# Lipo_Solar_Charger.net
KiCad netlist of a schematic drawn in Altium Designer
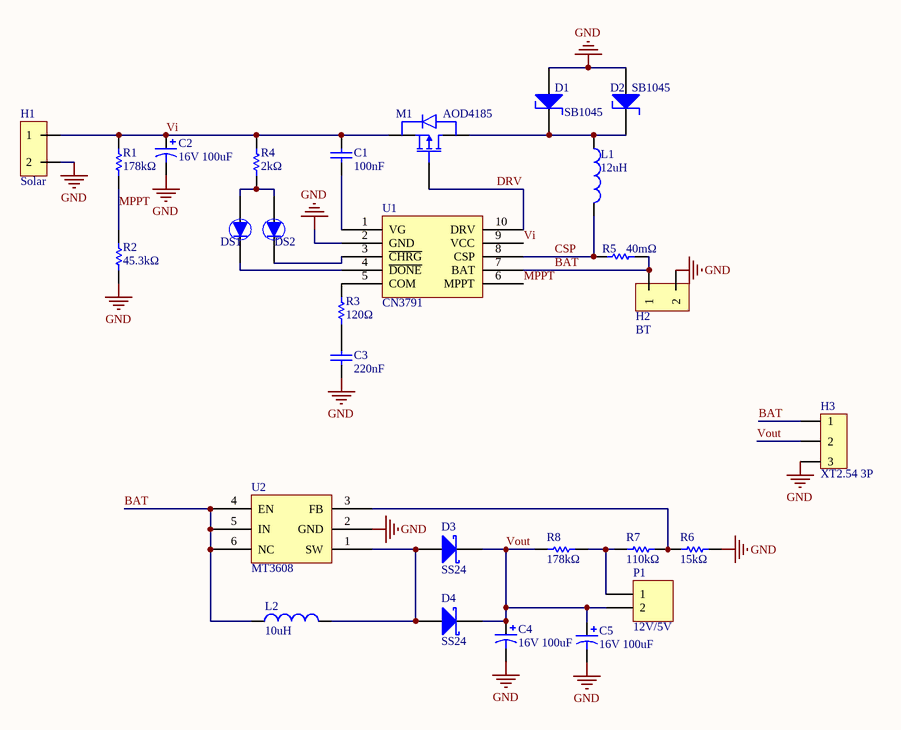
[diagram p0: Lipo_Solar_Charger.SchDoc]

(export (version "E")
  (design (tool "Eeschema 10.0.6"))
  (components
    (comp (ref "C1") (value "100nF") (footprint "0603") (libsource (lib "澄 library") (part "cap2")))
    (comp (ref "C2")
      (value "16V 100uF")
      (footprint "7343 Tantalum Capacitor")
      (description "有極性電容")
      (libsource (lib "澄 library") (part "cap"))
    )
    (comp (ref "C3") (value "220nF") (footprint "0603") (libsource (lib "澄 library") (part "cap2")))
    (comp (ref "C4")
      (value "16V 100uF")
      (footprint "7343 Tantalum Capacitor")
      (description "有極性電容")
      (libsource (lib "澄 library") (part "cap"))
    )
    (comp (ref "C5")
      (value "16V 100uF")
      (footprint "7343 Tantalum Capacitor")
      (description "有極性電容")
      (libsource (lib "澄 library") (part "cap"))
    )
    (comp (ref "D1")
      (value "SB1045")
      (footprint "TO-277")
      (description "10.0A SCHOTTKY BARRIER RECTIFIER")
      (libsource (lib "澄 library") (part "SB1045"))
    )
    (comp (ref "D2")
      (value "SB1045")
      (footprint "TO-277")
      (description "10.0A SCHOTTKY BARRIER RECTIFIER")
      (libsource (lib "澄 library") (part "SB1045"))
    )
    (comp (ref "D3")
      (value "SS24")
      (footprint "SMD Diode SMB")
      (description "Schottky Rectifier")
      (libsource (lib "澄 library") (part "DIODE"))
    )
    (comp (ref "D4")
      (value "SS24")
      (footprint "SMD Diode SMB")
      (description "Schottky Rectifier")
      (libsource (lib "澄 library") (part "DIODE"))
    )
    (comp (ref "DS1") (value "LED") (footprint "0603_LED") (libsource (lib "澄 library") (part "LED")))
    (comp (ref "DS2") (value "LED") (footprint "0603_LED") (libsource (lib "澄 library") (part "LED")))
    (comp (ref "H1") (value "Solar") (footprint "XH2.54 2P") (libsource (lib "") (part "XH2.54 2P_1")))
    (comp (ref "H2") (value "BT") (footprint "XH2.54 2P") (libsource (lib "澄 library") (part "XH2.54 2P")))
    (comp (ref "H3")
      (value "XT2.54 3P")
      (footprint "XH2.54 3P")
      (libsource (lib "澄 library") (part "XH2.54 3P"))
    )
    (comp (ref "L1") (value "12uH") (footprint "CDEP147") (libsource (lib "澄 library") (part "inductor_1")))
    (comp (ref "L2") (value "10uH") (footprint "CD75") (libsource (lib "澄 library") (part "inductor_1")))
    (comp (ref "M1")
      (value "AOD4185")
      (footprint "TO-252AA")
      (description "P-Channel Enhancement Mode Field Effect Transistor")
      (libsource (lib "澄 library") (part "AOD4185"))
    )
    (comp (ref "P1")
      (value "12V/5V")
      (footprint "HDR1X2")
      (description "Header, 2-Pin")
      (fields (field (name "PUBLISHER") "Altium Limited"))
      (libsource (lib "Miscellaneous Connectors") (part "Header 2"))
    )
    (comp (ref "R1")
      (value "178kΩ")
      (footprint "1608[0603]")
      (description "Resistor")
      (fields (field (name "PUBLISHER") "Altium Limited"))
      (libsource (lib "myLib2009") (part "Res"))
    )
    (comp (ref "R2")
      (value "45.3kΩ")
      (footprint "1608[0603]")
      (description "Resistor")
      (fields (field (name "PUBLISHER") "Altium Limited"))
      (libsource (lib "myLib2009") (part "Res"))
    )
    (comp (ref "R3")
      (value "120Ω")
      (footprint "1608[0603]")
      (description "Resistor")
      (fields (field (name "PUBLISHER") "Altium Limited"))
      (libsource (lib "myLib2009") (part "Res"))
    )
    (comp (ref "R4")
      (value "2kΩ")
      (footprint "1608[0603]")
      (description "Resistor")
      (fields (field (name "PUBLISHER") "Altium Limited"))
      (libsource (lib "myLib2009") (part "Res"))
    )
    (comp (ref "R5")
      (value "40mΩ")
      (footprint "2512[6432]")
      (description "R sense")
      (libsource (lib "澄 library") (part "Res"))
    )
    (comp (ref "R6")
      (value "15kΩ")
      (footprint "1608[0603]")
      (description "Resistor")
      (fields (field (name "PUBLISHER") "Altium Limited"))
      (libsource (lib "myLib2009") (part "Res"))
    )
    (comp (ref "R7")
      (value "110kΩ")
      (footprint "1608[0603]")
      (description "Resistor")
      (fields (field (name "PUBLISHER") "Altium Limited"))
      (libsource (lib "myLib2009") (part "Res"))
    )
    (comp (ref "R8")
      (value "178kΩ")
      (footprint "1608[0603]")
      (description "Resistor")
      (fields (field (name "PUBLISHER") "Altium Limited"))
      (libsource (lib "myLib2009") (part "Res"))
    )
    (comp (ref "U1")
      (value "CN3791")
      (footprint "SOIC100P600X175-10N")
      (description "4A, Standalone Li-ion Battery Charger IC  With Photovoltaic Cell MPPT Function")
      (libsource (lib "澄 library") (part "CN3791"))
    )
    (comp (ref "U2")
      (value "MT3608")
      (footprint "SOT23-6_L")
      (description "High Efficiency 1.2MHz  2A Step Up Converter")
      (libsource (lib "澄 library") (part "MT3608"))
    )
  )
  (nets
    (net (code "1") (name "/BAT") (class "Default")
      (node (ref "H2") (pin "1") (pinfunction "1_1") (pintype "power_in"))
      (node (ref "H3") (pin "1") (pinfunction "1_1") (pintype "passive"))
      (node (ref "L2") (pin "1") (pinfunction "1_1") (pintype "passive"))
      (node (ref "R5") (pin "1") (pinfunction "1_1") (pintype "passive"))
      (node (ref "U1") (pin "7") (pinfunction "BAT_7") (pintype "passive"))
      (node (ref "U2") (pin "4") (pinfunction "EN_4") (pintype "passive"))
      (node (ref "U2") (pin "5") (pinfunction "IN_5") (pintype "passive"))
      (node (ref "U2") (pin "6") (pinfunction "NC_6") (pintype "passive"))
    )
    (net (code "2") (name "/CSP") (class "Default")
      (node (ref "L1") (pin "2") (pinfunction "2_2") (pintype "passive"))
      (node (ref "R5") (pin "2") (pinfunction "2_2") (pintype "passive"))
      (node (ref "U1") (pin "8") (pinfunction "CSP_8") (pintype "passive"))
    )
    (net (code "3") (name "/DRV") (class "Default")
      (node (ref "M1") (pin "1") (pinfunction "G_1") (pintype "passive"))
      (node (ref "U1") (pin "10") (pinfunction "DRV_10") (pintype "passive"))
    )
    (net (code "4") (name "/MPPT") (class "Default")
      (node (ref "R1") (pin "1") (pinfunction "1_1") (pintype "passive"))
      (node (ref "R2") (pin "2") (pinfunction "2_2") (pintype "passive"))
      (node (ref "U1") (pin "6") (pinfunction "MPPT_6") (pintype "passive"))
    )
    (net (code "5") (name "/Vi") (class "Default")
      (node (ref "C1") (pin "2") (pinfunction "2_2") (pintype "passive"))
      (node (ref "C2") (pin "1") (pinfunction "1_1") (pintype "passive"))
      (node (ref "H1") (pin "1") (pinfunction "1_1") (pintype "power_in"))
      (node (ref "M1") (pin "3") (pinfunction "S_3") (pintype "passive"))
      (node (ref "R1") (pin "2") (pinfunction "2_2") (pintype "passive"))
      (node (ref "R4") (pin "2") (pinfunction "2_2") (pintype "passive"))
      (node (ref "U1") (pin "9") (pinfunction "VCC_9") (pintype "passive"))
    )
    (net (code "6") (name "/Vout") (class "Default")
      (node (ref "C4") (pin "1") (pinfunction "1_1") (pintype "passive"))
      (node (ref "C5") (pin "1") (pinfunction "1_1") (pintype "passive"))
      (node (ref "D3") (pin "2") (pinfunction "K_2") (pintype "passive"))
      (node (ref "D4") (pin "2") (pinfunction "K_2") (pintype "passive"))
      (node (ref "H3") (pin "2") (pinfunction "2_2") (pintype "passive"))
      (node (ref "P1") (pin "2") (pinfunction "2_2") (pintype "passive"))
      (node (ref "R8") (pin "2") (pinfunction "2_2") (pintype "passive"))
    )
    (net (code "7") (name "GND") (class "Default")
      (node (ref "C2") (pin "2") (pinfunction "2_2") (pintype "passive"))
      (node (ref "C3") (pin "1") (pinfunction "1_1") (pintype "passive"))
      (node (ref "C4") (pin "2") (pinfunction "2_2") (pintype "passive"))
      (node (ref "C5") (pin "2") (pinfunction "2_2") (pintype "passive"))
      (node (ref "D1") (pin "1") (pinfunction "A_1") (pintype "passive"))
      (node (ref "D2") (pin "1") (pinfunction "A_1") (pintype "passive"))
      (node (ref "H1") (pin "2") (pinfunction "2_2") (pintype "power_in"))
      (node (ref "H2") (pin "2") (pinfunction "2_2") (pintype "power_in"))
      (node (ref "H3") (pin "3") (pinfunction "3_3") (pintype "passive"))
      (node (ref "R2") (pin "1") (pinfunction "1_1") (pintype "passive"))
      (node (ref "R6") (pin "1") (pinfunction "1_1") (pintype "passive"))
      (node (ref "U1") (pin "2") (pinfunction "GND_2") (pintype "passive"))
      (node (ref "U2") (pin "2") (pinfunction "GND_2") (pintype "passive"))
    )
    (net (code "8") (name "Net-(C3-Pad2)") (class "Default")
      (node (ref "C3") (pin "2") (pinfunction "2_2") (pintype "passive"))
      (node (ref "R3") (pin "1") (pinfunction "1_1") (pintype "passive"))
    )
    (net (code "9") (name "Net-(D1-K)") (class "Default")
      (node (ref "D1") (pin "2") (pinfunction "K_2") (pintype "passive"))
      (node (ref "D2") (pin "2") (pinfunction "K_2") (pintype "passive"))
      (node (ref "L1") (pin "1") (pinfunction "1_1") (pintype "passive"))
      (node (ref "M1") (pin "2") (pinfunction "D_2") (pintype "passive"))
    )
    (net (code "10") (name "Net-(D3-A)") (class "Default")
      (node (ref "D3") (pin "1") (pinfunction "A_1") (pintype "passive"))
      (node (ref "D4") (pin "1") (pinfunction "A_1") (pintype "passive"))
      (node (ref "L2") (pin "2") (pinfunction "2_2") (pintype "passive"))
      (node (ref "U2") (pin "1") (pinfunction "SW_1") (pintype "passive"))
    )
    (net (code "11") (name "Net-(DS1-A)") (class "Default")
      (node (ref "DS1") (pin "1") (pinfunction "A_1") (pintype "passive"))
      (node (ref "DS2") (pin "1") (pinfunction "A_1") (pintype "passive"))
      (node (ref "R4") (pin "1") (pinfunction "1_1") (pintype "passive"))
    )
    (net (code "12") (name "Net-(DS1-K)") (class "Default")
      (node (ref "DS1") (pin "2") (pinfunction "K_2") (pintype "passive"))
      (node (ref "U1") (pin "4") (pinfunction "~{DONE}_4") (pintype "passive"))
    )
    (net (code "13") (name "Net-(DS2-K)") (class "Default")
      (node (ref "DS2") (pin "2") (pinfunction "K_2") (pintype "passive"))
      (node (ref "U1") (pin "3") (pinfunction "~{CHRG}_3") (pintype "passive"))
    )
    (net (code "14") (name "Net-(P1-Pad1)") (class "Default")
      (node (ref "P1") (pin "1") (pinfunction "1_1") (pintype "passive"))
      (node (ref "R7") (pin "2") (pinfunction "2_2") (pintype "passive"))
      (node (ref "R8") (pin "1") (pinfunction "1_1") (pintype "passive"))
    )
    (net (code "15") (name "Net-(U1-COM)") (class "Default")
      (node (ref "R3") (pin "2") (pinfunction "2_2") (pintype "passive"))
      (node (ref "U1") (pin "5") (pinfunction "COM_5") (pintype "passive"))
    )
    (net (code "16") (name "Net-(U1-VG)") (class "Default")
      (node (ref "C1") (pin "1") (pinfunction "1_1") (pintype "passive"))
      (node (ref "U1") (pin "1") (pinfunction "VG_1") (pintype "passive"))
    )
    (net (code "17") (name "Net-(U2-FB)") (class "Default")
      (node (ref "R6") (pin "2") (pinfunction "2_2") (pintype "passive"))
      (node (ref "R7") (pin "1") (pinfunction "1_1") (pintype "passive"))
      (node (ref "U2") (pin "3") (pinfunction "FB_3") (pintype "passive"))
    )
  )
)
